# RVP_OVP_LC.net
KiCad netlist of a schematic drawn in Altium Designer
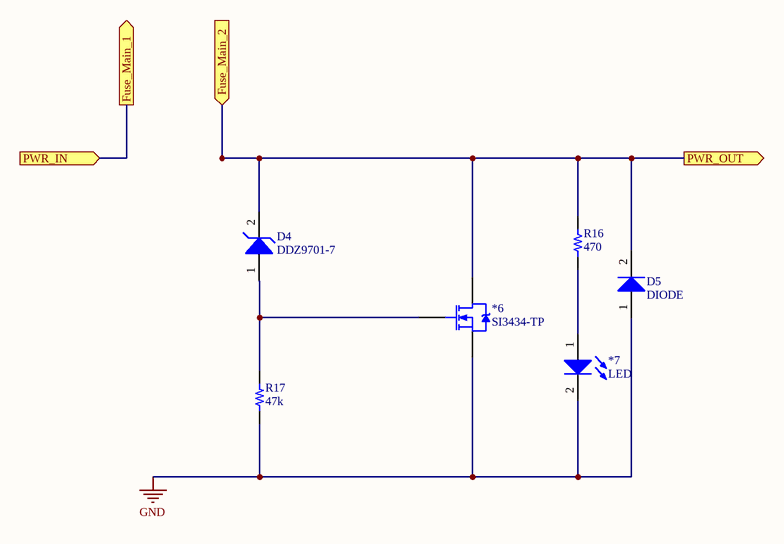
[diagram p0: RVP_OVP_LC.SchDoc]

(export (version "E")
  (design (tool "Eeschema 10.0.6"))
  (components
    (comp (ref "*6")
      (value "SI3434-TP")
      (footprint "SOT23-3")
      (description "MOSFET N-CHANNEL 30V 5A SOT23")
      (fields (field (name "CREATED_BY") "Angel"))
      (libsource (lib "Altium-Lib") (part "SI3434-TP"))
    )
    (comp (ref "*7") (value "LED") (footprint "0805_LED") (libsource (lib "Altium-Lib") (part "LED")))
    (comp (ref "D4")
      (value "DDZ9701-7")
      (footprint "SODFL350X115-2M")
      (description "Zener Diode 14V 500mW ±5% Surface Mount SOD-123")
      (fields (field (name "POWER") "500mW"))
      (libsource (lib "Altium-Lib") (part "Zener"))
    )
    (comp (ref "D5")
      (value "DIODE")
      (footprint "SOD-128")
      (description "DIODE SCHOTTKY 30V 5A TMINIP2")
      (fields (field (name "POWER") "30V") (field (name "MFRPARTNO") "DB2431200L"))
      (libsource (lib "Altium-Lib") (part "DIODE"))
    )
    (comp (ref "R16")
      (value "470")
      (footprint "RES 0805/2012")
      (fields
        (field (name "TOLERANCE") "1%")
        (field (name "POWER") "1/10W")
        (field (name "Comment") "Resistor 470 0805 1/10W 1%")
        (field (name "CREATED_BY") "Nick Mah")
      )
      (libsource (lib "Altium-Lib") (part "Resistor"))
    )
    (comp (ref "R17")
      (value "47k")
      (footprint "RES 0805/2012")
      (fields
        (field (name "TOLERANCE") "1%")
        (field (name "POWER") "1/10W")
        (field (name "Comment") "Resistor 47k 0805 1/10W 1%")
        (field (name "CREATED_BY") "Nick Mah")
      )
      (libsource (lib "Altium-Lib") (part "Resistor"))
    )
  )
  (nets
    (net (code "2") (name "/Fuse_Main_2") (class "Default")
      (node (ref "*6") (pin "3") (pinfunction "D_3") (pintype "passive"))
      (node (ref "D4") (pin "2") (pinfunction "K_2") (pintype "passive"))
      (node (ref "D5") (pin "2") (pinfunction "K_2") (pintype "passive"))
      (node (ref "R16") (pin "2") (pinfunction "2_2") (pintype "passive"))
    )
    (net (code "3") (name "GND") (class "Default")
      (node (ref "*6") (pin "2") (pinfunction "S_2") (pintype "passive"))
      (node (ref "*7") (pin "2") (pinfunction "K_2") (pintype "passive"))
      (node (ref "D5") (pin "1") (pinfunction "A_1") (pintype "passive"))
      (node (ref "R17") (pin "1") (pinfunction "1_1") (pintype "passive"))
    )
    (net (code "4") (name "Net-(*6-G)") (class "Default")
      (node (ref "*6") (pin "1") (pinfunction "G_1") (pintype "passive"))
      (node (ref "D4") (pin "1") (pinfunction "A_1") (pintype "passive"))
      (node (ref "R17") (pin "2") (pinfunction "2_2") (pintype "passive"))
    )
    (net (code "5") (name "Net-(*7-A)") (class "Default")
      (node (ref "*7") (pin "1") (pinfunction "A_1") (pintype "passive"))
      (node (ref "R16") (pin "1") (pinfunction "1_1") (pintype "passive"))
    )
  )
)
